# MX8M-Nano-Boot.net
KiCad netlist of a schematic drawn in Altium Designer
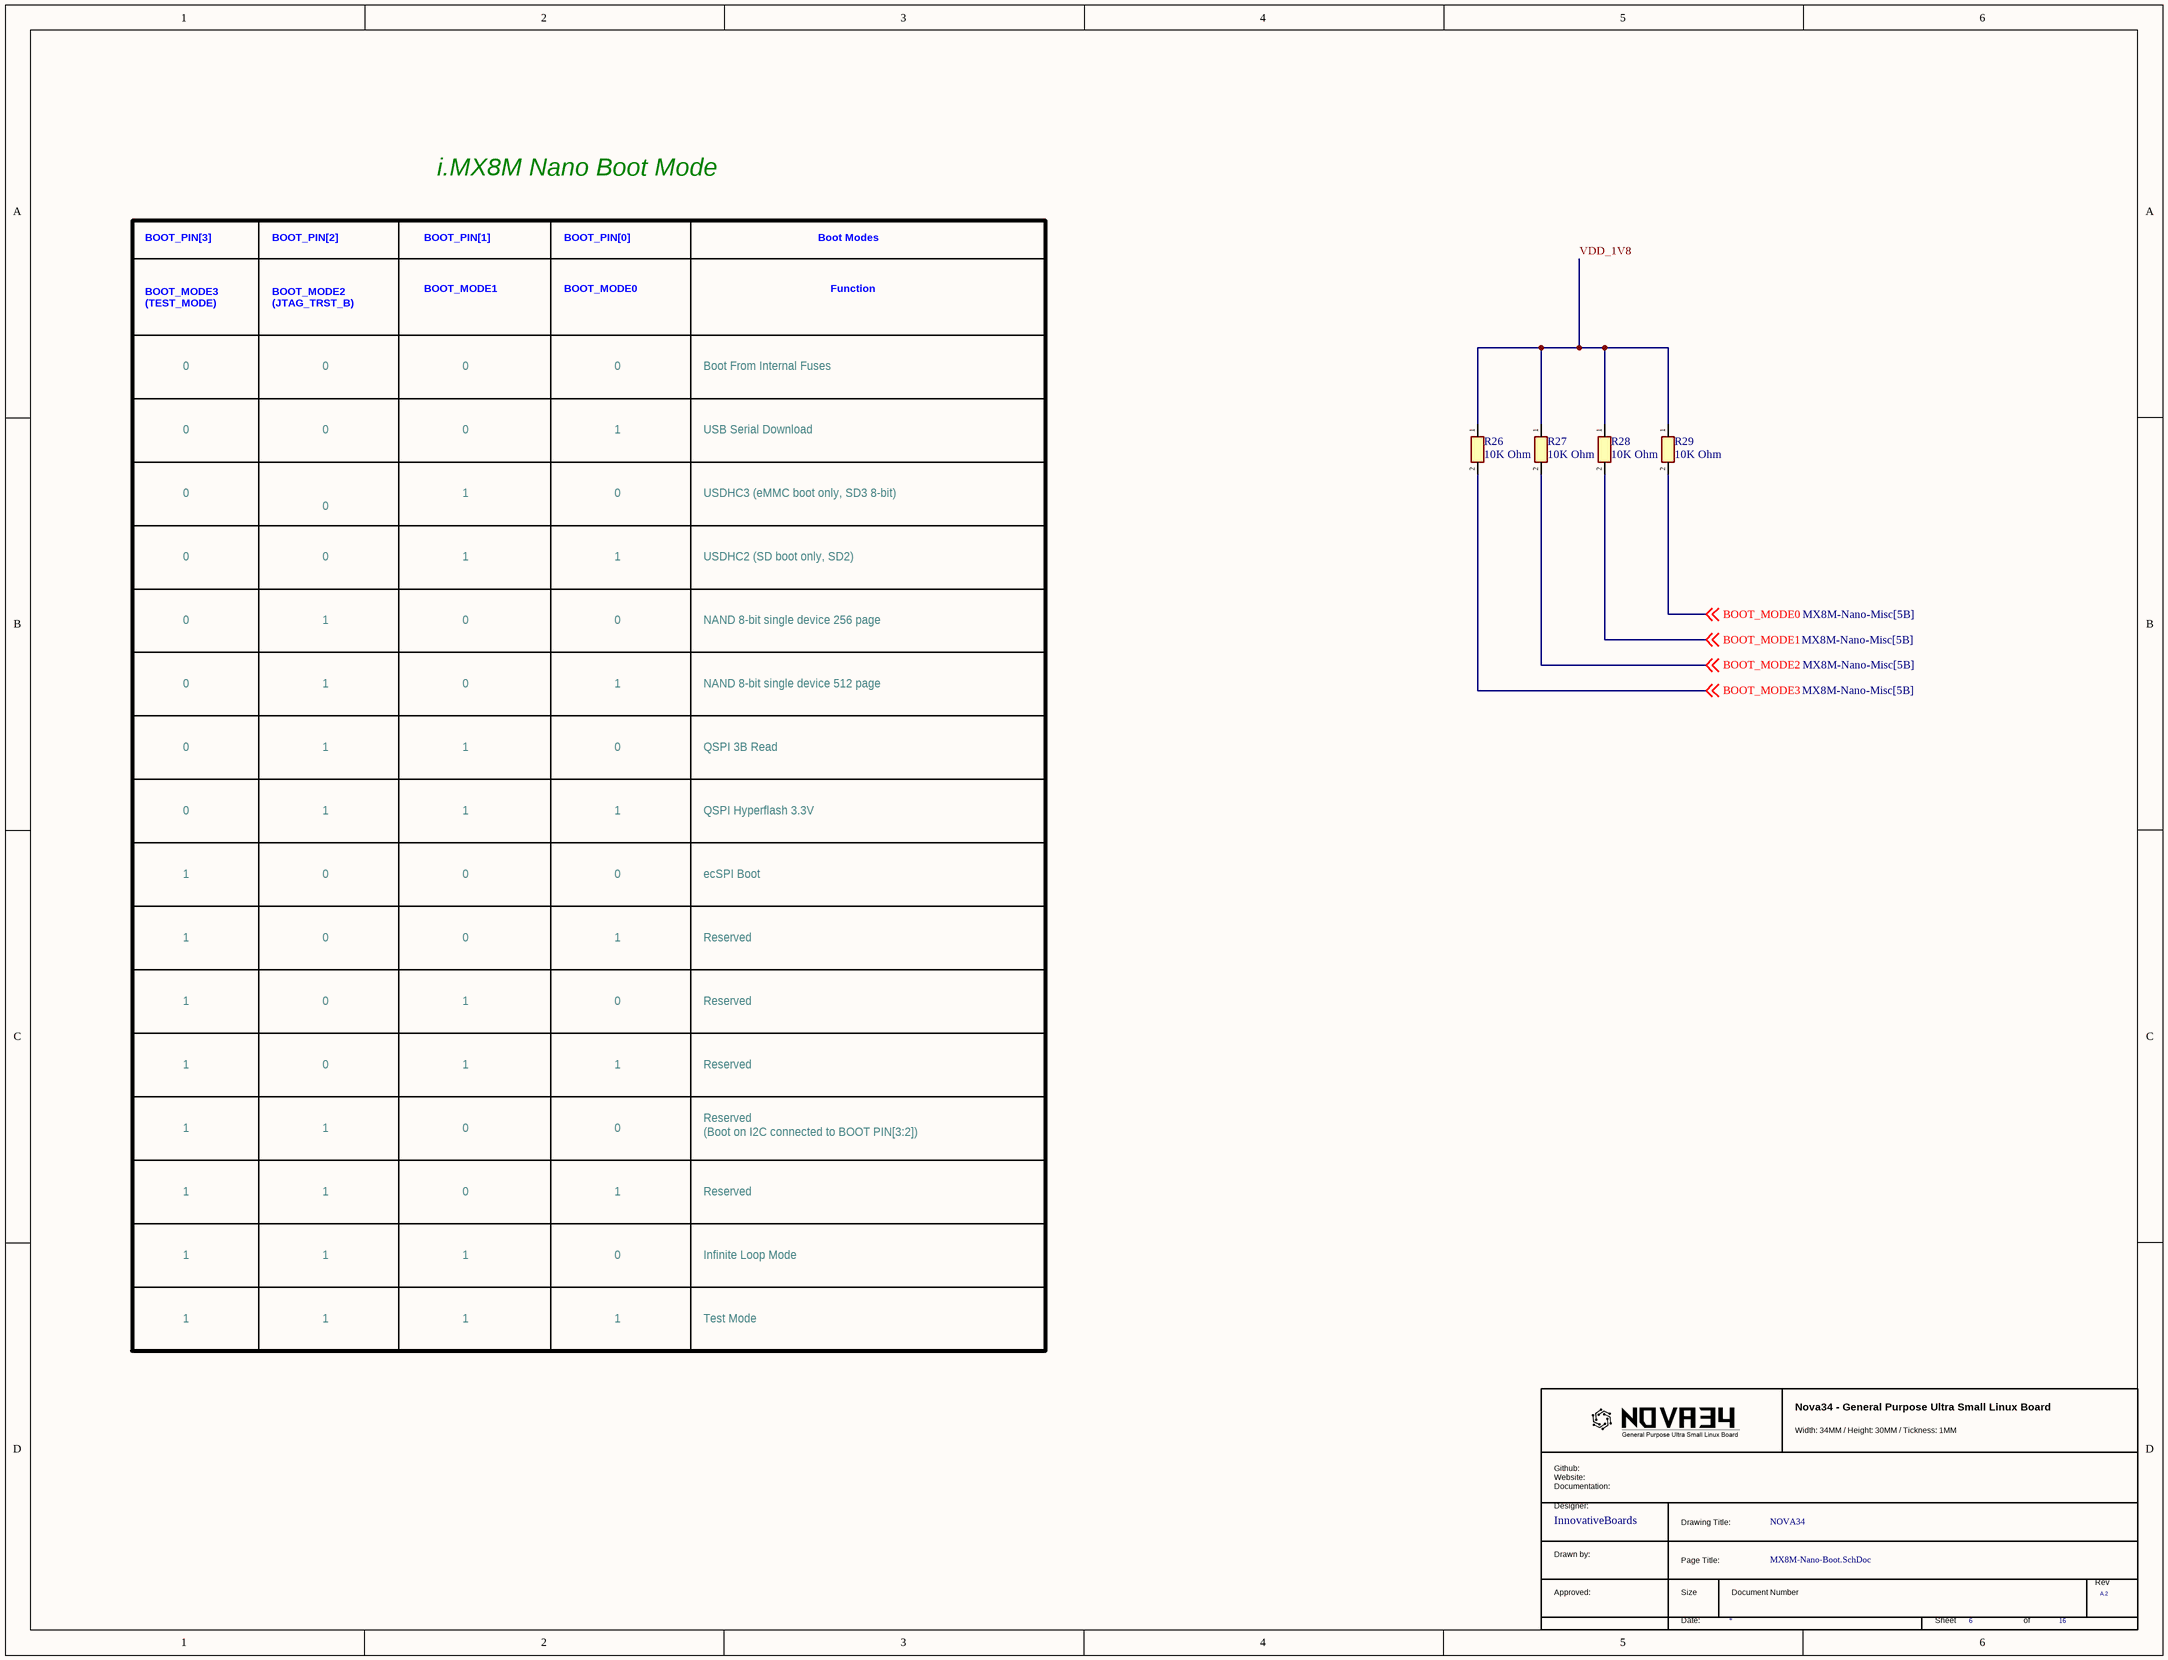
[diagram p0: MX8M-Nano-Boot.SchDoc]

(export (version "E")
  (design (tool "Eeschema 10.0.6"))
  (components
    (comp (ref "*")
      (value "TitleBlock_MCPG")
      (fields (field (name "REVCODE") "A.2"))
      (libsource (lib "Nova_SCHLIB") (part "TitleBlock_MCPG"))
    )
    (comp (ref "R26")
      (value "10K Ohm")
      (footprint "RESC1005X40N")
      (description "Resistor")
      (fields
        (field (name "MANUFACTURER_PART_NUMBER") "RC0402FR-0710KL")
        (field (name "MOUSER PART NUMBER") "603-RC0402FR-0710KL")
      )
      (libsource (lib "Nova_SCHLIB") (part "RC0402FR-0710KL"))
    )
    (comp (ref "R27")
      (value "10K Ohm")
      (footprint "RESC1005X40N")
      (description "Resistor")
      (fields
        (field (name "MANUFACTURER_PART_NUMBER") "RC0402FR-0710KL")
        (field (name "MOUSER PART NUMBER") "603-RC0402FR-0710KL")
      )
      (libsource (lib "Nova_SCHLIB") (part "RC0402FR-0710KL"))
    )
    (comp (ref "R28")
      (value "10K Ohm")
      (footprint "RESC1005X40N")
      (description "Resistor")
      (fields
        (field (name "MANUFACTURER_PART_NUMBER") "RC0402FR-0710KL")
        (field (name "MOUSER PART NUMBER") "603-RC0402FR-0710KL")
      )
      (libsource (lib "Nova_SCHLIB") (part "RC0402FR-0710KL"))
    )
    (comp (ref "R29")
      (value "10K Ohm")
      (footprint "RESC1005X40N")
      (description "Resistor")
      (fields
        (field (name "MANUFACTURER_PART_NUMBER") "RC0402FR-0710KL")
        (field (name "MOUSER PART NUMBER") "603-RC0402FR-0710KL")
      )
      (libsource (lib "Nova_SCHLIB") (part "RC0402FR-0710KL"))
    )
  )
  (nets
    (net (code "1") (name "/VDD_1V8") (class "Default")
      (node (ref "R26") (pin "1") (pinfunction "1_1") (pintype "passive"))
      (node (ref "R27") (pin "1") (pinfunction "1_1") (pintype "passive"))
      (node (ref "R28") (pin "1") (pinfunction "1_1") (pintype "passive"))
      (node (ref "R29") (pin "1") (pinfunction "1_1") (pintype "passive"))
    )
    (net (code "2") (name "BOOT_MODE0") (class "Default")
      (node (ref "R29") (pin "2") (pinfunction "2_2") (pintype "passive"))
    )
    (net (code "3") (name "BOOT_MODE1") (class "Default")
      (node (ref "R28") (pin "2") (pinfunction "2_2") (pintype "passive"))
    )
    (net (code "4") (name "BOOT_MODE2") (class "Default")
      (node (ref "R27") (pin "2") (pinfunction "2_2") (pintype "passive"))
    )
    (net (code "5") (name "BOOT_MODE3") (class "Default")
      (node (ref "R26") (pin "2") (pinfunction "2_2") (pintype "passive"))
    )
  )
)
